# Main.net
KiCad netlist of a schematic drawn in Altium Designer
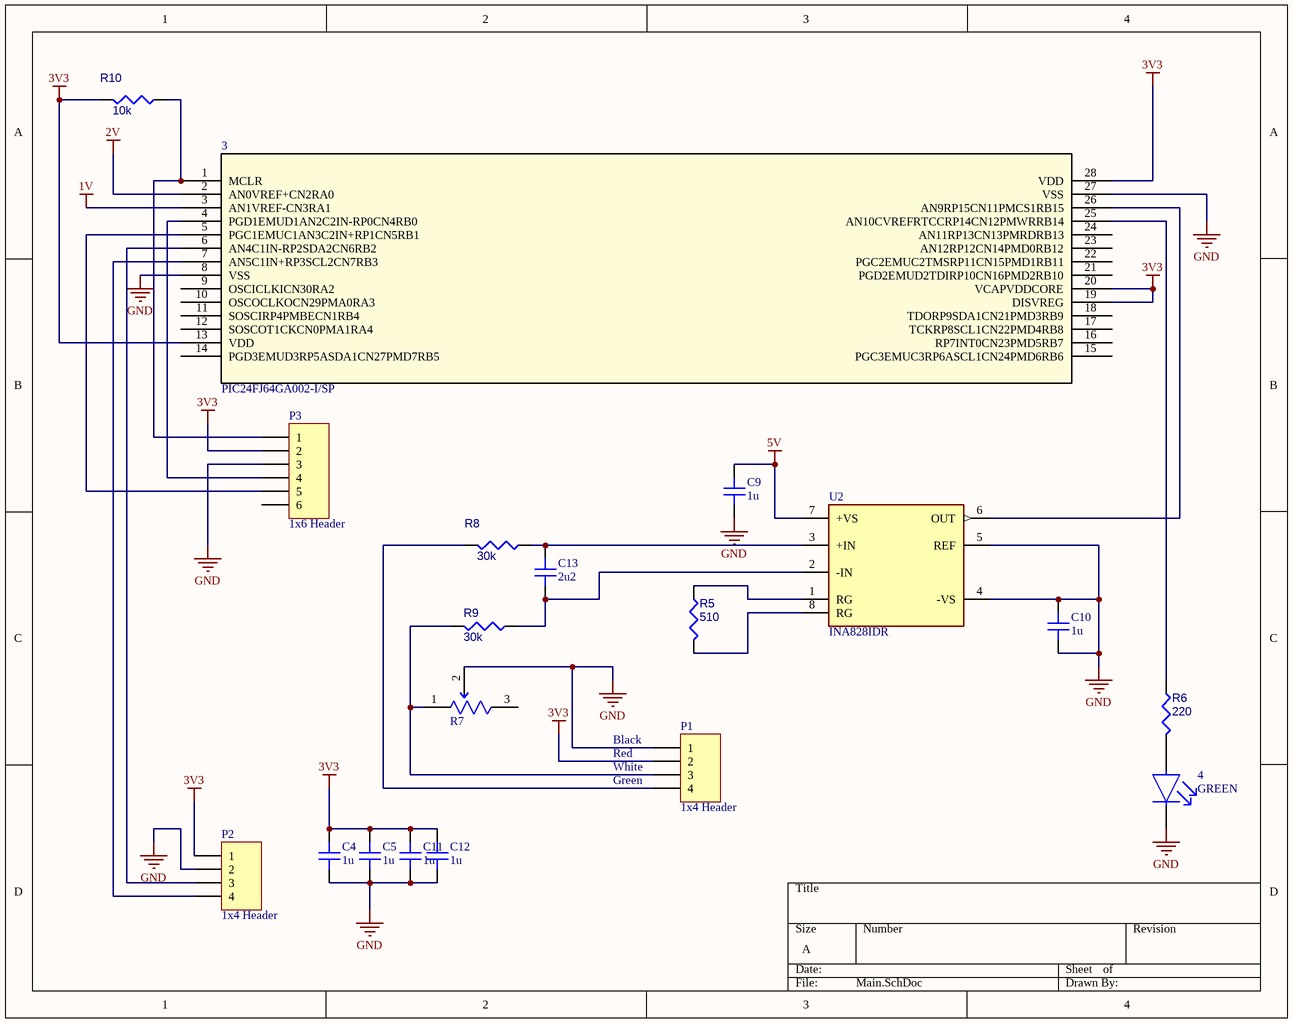
[diagram p0: Main.SchDoc]

(export (version "E")
  (design (tool "Eeschema 10.0.6"))
  (components
    (comp (ref "3")
      (value "PIC24FJ64GA002-I/SP")
      (footprint "DIP787W46P254L3467H508Q28")
      (description "PIC PICÂ® 24F Microcontroller IC 16-Bit 32MHz 64KB _22K x 24_ FLASH 28-SPDIP")
      (fields (field (name "MF") "Microchip"))
      (libsource (lib "Gopher Motorsports") (part "PIC24FJ64GA002-I/SP"))
    )
    (comp (ref "4")
      (value "GREEN")
      (footprint "FP-ASMT-RF45-AN002-MFG")
      (description "ASMT-RF45-AN002 LED YLW/GREEN DIFFUSED 0603 SMD")
      (fields
        (field (name "MANUFACTURER") "Broadcom")
        (field (name "OCTOPART") "https://octopart.com/asmt-rf45-an002-broadcom-71127304")
      )
      (libsource (lib "Altium Content Vault") (part "8706943c75ba83719d021d2fdc84c58"))
    )
    (comp (ref "C4")
      (value "1u")
      (footprint "CAP 0603_1608")
      (fields
        (field (name "PART NUMBER") "ZRB18AR6YA475ME05L")
        (field (name "MANUFACTURER") "Murata Electronics")
        (field (name "TOLERANCE") "±20%")
      )
      (libsource (lib "Gopher Motorsports") (part "CAPACITOR"))
    )
    (comp (ref "C5")
      (value "1u")
      (footprint "CAP 0603_1608")
      (fields
        (field (name "PART NUMBER") "ZRB18AR6YA475ME05L")
        (field (name "MANUFACTURER") "Murata Electronics")
        (field (name "TOLERANCE") "±20%")
      )
      (libsource (lib "Gopher Motorsports") (part "CAPACITOR"))
    )
    (comp (ref "C9")
      (value "1u")
      (footprint "CAP 0603_1608")
      (fields
        (field (name "PART NUMBER") "ZRB18AR6YA475ME05L")
        (field (name "MANUFACTURER") "Murata Electronics")
        (field (name "TOLERANCE") "±20%")
      )
      (libsource (lib "Gopher Motorsports") (part "CAPACITOR"))
    )
    (comp (ref "C10")
      (value "1u")
      (footprint "CAP 0603_1608")
      (fields
        (field (name "PART NUMBER") "ZRB18AR6YA475ME05L")
        (field (name "MANUFACTURER") "Murata Electronics")
        (field (name "TOLERANCE") "±20%")
      )
      (libsource (lib "Gopher Motorsports") (part "CAPACITOR"))
    )
    (comp (ref "C11")
      (value "1u")
      (footprint "CAP 0603_1608")
      (fields
        (field (name "PART NUMBER") "ZRB18AR6YA475ME05L")
        (field (name "MANUFACTURER") "Murata Electronics")
        (field (name "TOLERANCE") "±20%")
      )
      (libsource (lib "Gopher Motorsports") (part "CAPACITOR"))
    )
    (comp (ref "C12")
      (value "1u")
      (footprint "CAP 0603_1608")
      (fields
        (field (name "PART NUMBER") "ZRB18AR6YA475ME05L")
        (field (name "MANUFACTURER") "Murata Electronics")
        (field (name "TOLERANCE") "±20%")
      )
      (libsource (lib "Gopher Motorsports") (part "CAPACITOR"))
    )
    (comp (ref "C13")
      (value "2u2")
      (footprint "CAP 0603_1608")
      (fields
        (field (name "PART NUMBER") "ZRB18AR6YA475ME05L")
        (field (name "MANUFACTURER") "Murata Electronics")
        (field (name "TOLERANCE") "±20%")
      )
      (libsource (lib "Gopher Motorsports") (part "CAPACITOR"))
    )
    (comp (ref "P1")
      (value "1x4 Header")
      (footprint "1x4 Header")
      (description "Male Header, Dupont, 1x4")
      (libsource (lib "Gopher Motorsports") (part "1x4 Header"))
    )
    (comp (ref "P2")
      (value "1x4 Header")
      (footprint "1x4 Header")
      (description "Male Header, Dupont, 1x4")
      (libsource (lib "Gopher Motorsports") (part "1x4 Header"))
    )
    (comp (ref "P3")
      (value "1x6 Header")
      (footprint "1x6 Header")
      (description "Male Header, Dupont, 1x6")
      (libsource (lib "Gopher Motorsports") (part "1x6 Header"))
    )
    (comp (ref "R5")
      (value "510")
      (footprint "RESC1608X55X25ML10T15")
      (description "Chip Resistor, +/-1%, 0.1 W, -55 to 155 degC, 0603 (1608 Metric)")
      (fields (field (name "POWER") "100mW") (field (name "TOLERANCE") "1%"))
      (libsource (lib "Gopher Motorsports") (part "RES-2"))
    )
    (comp (ref "R6")
      (value "220")
      (footprint "RESC1608X55X25ML10T15")
      (description "Chip Resistor, +/-1%, 0.1 W, -55 to 155 degC, 0603 (1608 Metric)")
      (fields (field (name "POWER") "100mW") (field (name "TOLERANCE") "1%"))
      (libsource (lib "Gopher Motorsports") (part "RES-2"))
    )
    (comp (ref "R7")
      (value "PV36W501C01B00")
      (footprint "FP-PV36W-MFG")
      (description "Trimmer")
      (libsource (lib "Gopher Motorsports") (part "d579d08a39777ccaa720d62023d89b1"))
    )
    (comp (ref "R8")
      (value "30k")
      (footprint "RESC1608X55X25ML10T15")
      (description "Chip Resistor, +/-1%, 0.1 W, -55 to 155 degC, 0603 (1608 Metric)")
      (fields (field (name "POWER") "100mW") (field (name "TOLERANCE") "1%"))
      (libsource (lib "Gopher Motorsports") (part "RES-2"))
    )
    (comp (ref "R9")
      (value "30k")
      (footprint "RESC1608X55X25ML10T15")
      (description "Chip Resistor, +/-1%, 0.1 W, -55 to 155 degC, 0603 (1608 Metric)")
      (fields (field (name "POWER") "100mW") (field (name "TOLERANCE") "1%"))
      (libsource (lib "Gopher Motorsports") (part "RES-2"))
    )
    (comp (ref "R10")
      (value "10k")
      (footprint "RESC1608X55X25ML10T15")
      (description "Chip Resistor, +/-1%, 0.1 W, -55 to 155 degC, 0603 (1608 Metric)")
      (fields (field (name "POWER") "100mW") (field (name "TOLERANCE") "1%"))
      (libsource (lib "Gopher Motorsports") (part "RES-2"))
    )
    (comp (ref "U2")
      (value "INA828IDR")
      (footprint "FP-D0008A-IPC_B")
      (description "Instrumentation Amplifier, 1 Func, 90uV Offset-Max, 2MHz Band Width, PDSO8")
      (libsource (lib "Gopher Motorsports") (part "fa082fdca6ccd95e01d5e82d11f3155"))
    )
  )
  (nets
    (net (code "1") (name "1V") (class "Default")
      (node (ref "3") (pin "3") (pinfunction "AN1VREF-CN3RA1_3") (pintype "passive"))
    )
    (net (code "2") (name "2V") (class "Default")
      (node (ref "3") (pin "2") (pinfunction "AN0VREF+CN2RA0_2") (pintype "passive"))
    )
    (net (code "3") (name "3V3") (class "Default")
      (node (ref "3") (pin "13") (pinfunction "VDD_13") (pintype "passive"))
      (node (ref "3") (pin "19") (pinfunction "DISVREG_19") (pintype "passive"))
      (node (ref "3") (pin "20") (pinfunction "VCAPVDDCORE_20") (pintype "passive"))
      (node (ref "3") (pin "28") (pinfunction "VDD_28") (pintype "passive"))
      (node (ref "C11") (pin "2") (pinfunction "2_2") (pintype "passive"))
      (node (ref "C12") (pin "2") (pinfunction "2_2") (pintype "passive"))
      (node (ref "C4") (pin "2") (pinfunction "2_2") (pintype "passive"))
      (node (ref "C5") (pin "2") (pinfunction "2_2") (pintype "passive"))
      (node (ref "P1") (pin "2") (pinfunction "2_2") (pintype "passive"))
      (node (ref "P2") (pin "1") (pinfunction "1_1") (pintype "passive"))
      (node (ref "P3") (pin "2") (pinfunction "2_2") (pintype "passive"))
      (node (ref "R10") (pin "2") (pinfunction "2_2") (pintype "passive"))
    )
    (net (code "4") (name "5V") (class "Default")
      (node (ref "C9") (pin "2") (pinfunction "2_2") (pintype "passive"))
      (node (ref "U2") (pin "7") (pinfunction "+VS_7") (pintype "power_in"))
    )
    (net (code "5") (name "GND") (class "Default")
      (node (ref "3") (pin "27") (pinfunction "VSS_27") (pintype "passive"))
      (node (ref "3") (pin "8") (pinfunction "VSS_8") (pintype "passive"))
      (node (ref "4") (pin "1") (pinfunction "C_1") (pintype "passive"))
      (node (ref "C10") (pin "1") (pinfunction "1_1") (pintype "passive"))
      (node (ref "C10") (pin "2") (pinfunction "2_2") (pintype "passive"))
      (node (ref "C11") (pin "1") (pinfunction "1_1") (pintype "passive"))
      (node (ref "C12") (pin "1") (pinfunction "1_1") (pintype "passive"))
      (node (ref "C4") (pin "1") (pinfunction "1_1") (pintype "passive"))
      (node (ref "C5") (pin "1") (pinfunction "1_1") (pintype "passive"))
      (node (ref "C9") (pin "1") (pinfunction "1_1") (pintype "passive"))
      (node (ref "P1") (pin "1") (pinfunction "1_1") (pintype "passive"))
      (node (ref "P2") (pin "2") (pinfunction "2_2") (pintype "passive"))
      (node (ref "P3") (pin "3") (pinfunction "3_3") (pintype "passive"))
      (node (ref "R7") (pin "2") (pinfunction "2_2") (pintype "passive"))
      (node (ref "U2") (pin "4") (pinfunction "-VS_4") (pintype "power_in"))
      (node (ref "U2") (pin "5") (pinfunction "REF_5") (pintype "power_in"))
    )
    (net (code "6") (name "Net-(3-AN4C1IN-RP2SDA2CN6RB2)") (class "Default")
      (node (ref "3") (pin "6") (pinfunction "AN4C1IN-RP2SDA2CN6RB2_6") (pintype "passive"))
      (node (ref "P2") (pin "3") (pinfunction "3_3") (pintype "passive"))
    )
    (net (code "7") (name "Net-(3-AN5C1IN+RP3SCL2CN7RB3)") (class "Default")
      (node (ref "3") (pin "7") (pinfunction "AN5C1IN+RP3SCL2CN7RB3_7") (pintype "passive"))
      (node (ref "P2") (pin "4") (pinfunction "4_4") (pintype "passive"))
    )
    (net (code "8") (name "Net-(3-AN9RP15CN11PMCS1RB15)") (class "Default")
      (node (ref "3") (pin "26") (pinfunction "AN9RP15CN11PMCS1RB15_26") (pintype "passive"))
      (node (ref "U2") (pin "6") (pinfunction "OUT_6") (pintype "output"))
    )
    (net (code "9") (name "Net-(3-AN10CVREFRTCCRP14CN12PMWRRB14)") (class "Default")
      (node (ref "3") (pin "25") (pinfunction "AN10CVREFRTCCRP14CN12PMWRRB14_25") (pintype "passive"))
      (node (ref "R6") (pin "1") (pinfunction "1_1") (pintype "passive"))
    )
    (net (code "10") (name "Net-(3-MCLR)") (class "Default")
      (node (ref "3") (pin "1") (pinfunction "MCLR_1") (pintype "passive"))
      (node (ref "P3") (pin "1") (pinfunction "1_1") (pintype "passive"))
      (node (ref "R10") (pin "1") (pinfunction "1_1") (pintype "passive"))
    )
    (net (code "11") (name "Net-(3-PGC1EMUC1AN3C2IN+RP1CN5RB1)") (class "Default")
      (node (ref "3") (pin "5") (pinfunction "PGC1EMUC1AN3C2IN+RP1CN5RB1_5") (pintype "passive"))
      (node (ref "P3") (pin "5") (pinfunction "5_5") (pintype "passive"))
    )
    (net (code "12") (name "Net-(3-PGD1EMUD1AN2C2IN-RP0CN4RB0)") (class "Default")
      (node (ref "3") (pin "4") (pinfunction "PGD1EMUD1AN2C2IN-RP0CN4RB0_4") (pintype "passive"))
      (node (ref "P3") (pin "4") (pinfunction "4_4") (pintype "passive"))
    )
    (net (code "13") (name "Net-(4-A)") (class "Default")
      (node (ref "4") (pin "2") (pinfunction "A_2") (pintype "passive"))
      (node (ref "R6") (pin "2") (pinfunction "2_2") (pintype "passive"))
    )
    (net (code "14") (name "Net-(P1-Pad3)") (class "Default")
      (node (ref "P1") (pin "3") (pinfunction "3_3") (pintype "passive"))
      (node (ref "R7") (pin "1") (pinfunction "1_1") (pintype "passive"))
      (node (ref "R9") (pin "2") (pinfunction "2_2") (pintype "passive"))
    )
    (net (code "15") (name "Net-(P1-Pad4)") (class "Default")
      (node (ref "P1") (pin "4") (pinfunction "4_4") (pintype "passive"))
      (node (ref "R8") (pin "2") (pinfunction "2_2") (pintype "passive"))
    )
    (net (code "16") (name "Net-(R5-Pad1)") (class "Default")
      (node (ref "R5") (pin "1") (pinfunction "1_1") (pintype "passive"))
      (node (ref "U2") (pin "1") (pinfunction "RG_1") (pintype "passive"))
    )
    (net (code "17") (name "Net-(R5-Pad2)") (class "Default")
      (node (ref "R5") (pin "2") (pinfunction "2_2") (pintype "passive"))
      (node (ref "U2") (pin "8") (pinfunction "RG_8") (pintype "passive"))
    )
    (net (code "18") (name "Net-(U2-+IN)") (class "Default")
      (node (ref "C13") (pin "2") (pinfunction "2_2") (pintype "passive"))
      (node (ref "R8") (pin "1") (pinfunction "1_1") (pintype "passive"))
      (node (ref "U2") (pin "3") (pinfunction "+IN_3") (pintype "tri_state"))
    )
    (net (code "19") (name "Net-(U2--IN)") (class "Default")
      (node (ref "C13") (pin "1") (pinfunction "1_1") (pintype "passive"))
      (node (ref "R9") (pin "1") (pinfunction "1_1") (pintype "passive"))
      (node (ref "U2") (pin "2") (pinfunction "-IN_2") (pintype "tri_state"))
    )
    (net (code "20") (name "unconnected-(3-AN11RP13CN13PMRDRB13-Pad24)") (class "Default")
      (node (ref "3") (pin "24") (pinfunction "AN11RP13CN13PMRDRB13_24") (pintype "passive"))
    )
    (net (code "21") (name "unconnected-(3-AN12RP12CN14PMD0RB12-Pad23)") (class "Default")
      (node (ref "3") (pin "23") (pinfunction "AN12RP12CN14PMD0RB12_23") (pintype "passive"))
    )
    (net (code "22") (name "unconnected-(3-OSCICLKICN30RA2-Pad9)") (class "Default")
      (node (ref "3") (pin "9") (pinfunction "OSCICLKICN30RA2_9") (pintype "passive"))
    )
    (net (code "23") (name "unconnected-(3-OSCOCLKOCN29PMA0RA3-Pad10)") (class "Default")
      (node (ref "3") (pin "10") (pinfunction "OSCOCLKOCN29PMA0RA3_10") (pintype "passive"))
    )
    (net (code "24") (name "unconnected-(3-PGC2EMUC2TMSRP11CN15PMD1RB11-Pad22)") (class "Default")
      (node (ref "3") (pin "22") (pinfunction "PGC2EMUC2TMSRP11CN15PMD1RB11_22") (pintype "passive"))
    )
    (net (code "25") (name "unconnected-(3-PGC3EMUC3RP6ASCL1CN24PMD6RB6-Pad15)") (class "Default")
      (node (ref "3") (pin "15") (pinfunction "PGC3EMUC3RP6ASCL1CN24PMD6RB6_15") (pintype "passive"))
    )
    (net (code "26") (name "unconnected-(3-PGD2EMUD2TDIRP10CN16PMD2RB10-Pad21)") (class "Default")
      (node (ref "3") (pin "21") (pinfunction "PGD2EMUD2TDIRP10CN16PMD2RB10_21") (pintype "passive"))
    )
    (net (code "27") (name "unconnected-(3-PGD3EMUD3RP5ASDA1CN27PMD7RB5-Pad14)") (class "Default")
      (node (ref "3") (pin "14") (pinfunction "PGD3EMUD3RP5ASDA1CN27PMD7RB5_14") (pintype "passive"))
    )
    (net (code "28") (name "unconnected-(3-RP7INT0CN23PMD5RB7-Pad16)") (class "Default")
      (node (ref "3") (pin "16") (pinfunction "RP7INT0CN23PMD5RB7_16") (pintype "passive"))
    )
    (net (code "29") (name "unconnected-(3-SOSCIRP4PMBECN1RB4-Pad11)") (class "Default")
      (node (ref "3") (pin "11") (pinfunction "SOSCIRP4PMBECN1RB4_11") (pintype "passive"))
    )
    (net (code "30") (name "unconnected-(3-SOSCOT1CKCN0PMA1RA4-Pad12)") (class "Default")
      (node (ref "3") (pin "12") (pinfunction "SOSCOT1CKCN0PMA1RA4_12") (pintype "passive"))
    )
    (net (code "31") (name "unconnected-(3-TCKRP8SCL1CN22PMD4RB8-Pad17)") (class "Default")
      (node (ref "3") (pin "17") (pinfunction "TCKRP8SCL1CN22PMD4RB8_17") (pintype "passive"))
    )
    (net (code "32") (name "unconnected-(3-TDORP9SDA1CN21PMD3RB9-Pad18)") (class "Default")
      (node (ref "3") (pin "18") (pinfunction "TDORP9SDA1CN21PMD3RB9_18") (pintype "passive"))
    )
    (net (code "33") (name "unconnected-(P3-Pad6)") (class "Default")
      (node (ref "P3") (pin "6") (pinfunction "6_6") (pintype "passive"))
    )
    (net (code "34") (name "unconnected-(R7-Pad3)") (class "Default")
      (node (ref "R7") (pin "3") (pinfunction "3_3") (pintype "passive"))
    )
  )
)
